# UperMachine.net
KiCad netlist of a schematic drawn in Altium Designer
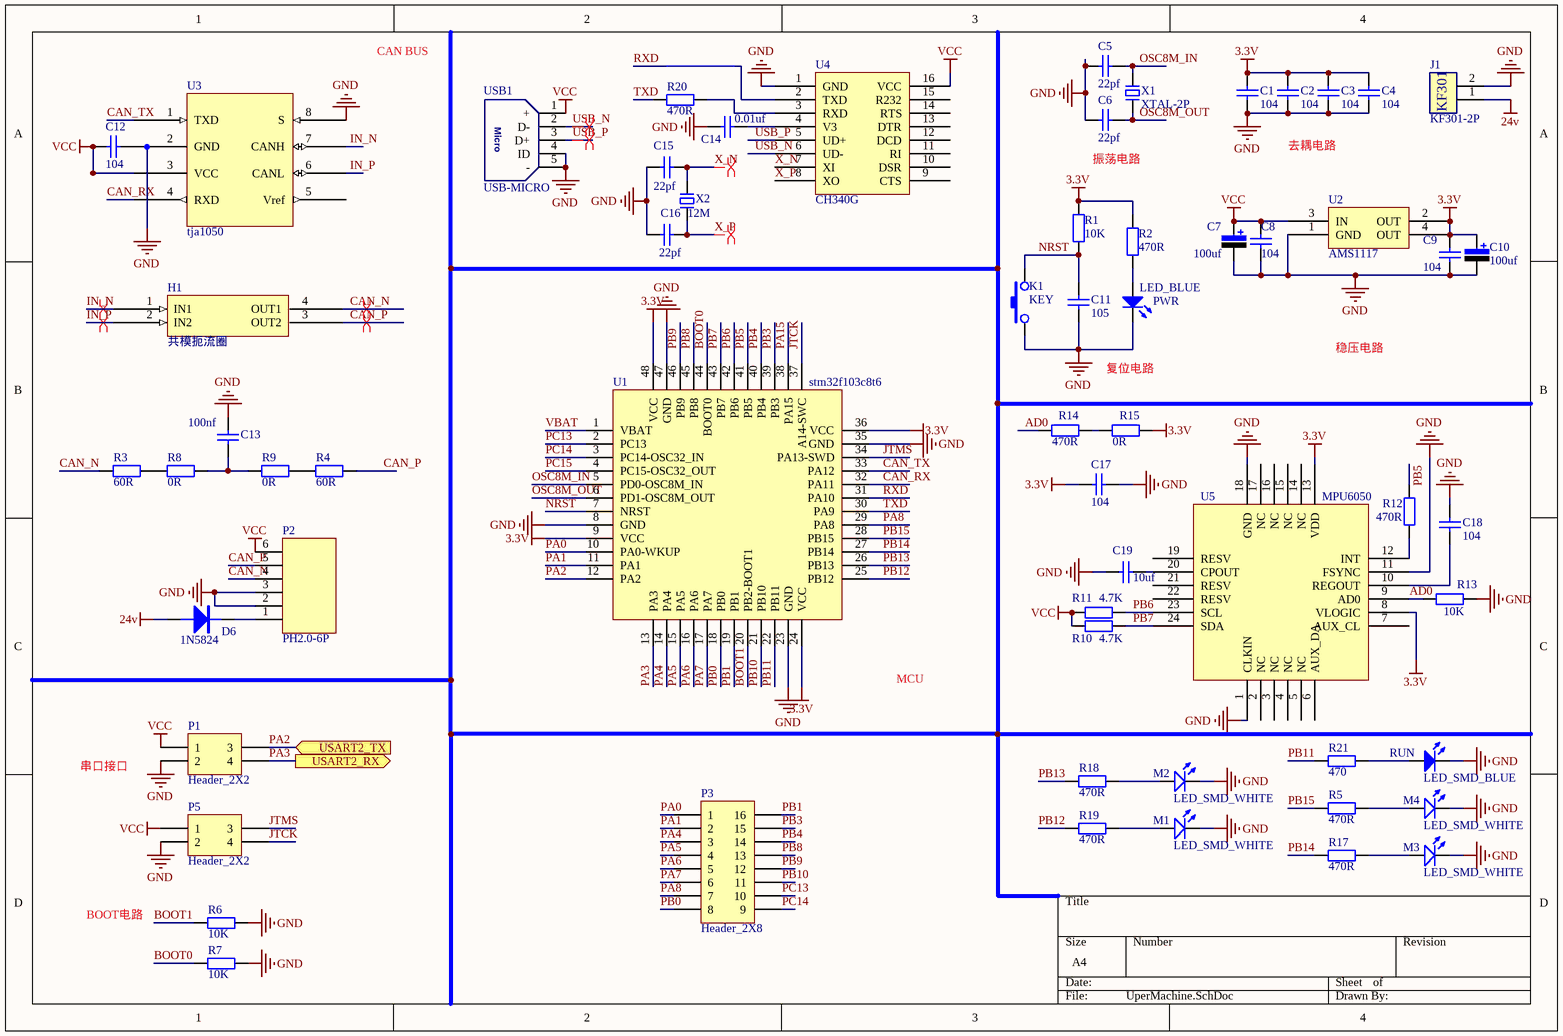
[diagram p0: UperMachine.SchDoc]

(export (version "E")
  (design (tool "Eeschema 10.0.6"))
  (components
    (comp (ref "C1") (value "104") (footprint "Cap-0603") (libsource (lib "最小系统元件库") (part "CAP")))
    (comp (ref "C2") (value "104") (footprint "Cap-0603") (libsource (lib "最小系统元件库") (part "CAP")))
    (comp (ref "C3") (value "104") (footprint "Cap-0603") (libsource (lib "最小系统元件库") (part "CAP")))
    (comp (ref "C4") (value "104") (footprint "Cap-0603") (libsource (lib "最小系统元件库") (part "CAP")))
    (comp (ref "C5") (value "22pf") (footprint "Cap-0603") (libsource (lib "最小系统元件库") (part "CAP")))
    (comp (ref "C6") (value "22pf") (footprint "Cap-0603") (libsource (lib "最小系统元件库") (part "CAP")))
    (comp (ref "C7") (value "100uf") (footprint "tan_cap_C") (libsource (lib "最小系统元件库") (part "tan_cap")))
    (comp (ref "C8") (value "104") (footprint "Cap-0603-M") (libsource (lib "最小系统元件库") (part "CAP")))
    (comp (ref "C9") (value "104") (footprint "Cap-0603-M") (libsource (lib "最小系统元件库") (part "CAP")))
    (comp (ref "C10") (value "100uf") (footprint "tan_cap_C") (libsource (lib "最小系统元件库") (part "tan_cap")))
    (comp (ref "C11") (value "105") (footprint "Cap-0603") (libsource (lib "最小系统元件库") (part "CAP")))
    (comp (ref "C12") (value "104") (footprint "Cap-0603") (libsource (lib "最小系统元件库") (part "CAP")))
    (comp (ref "C13") (value "100nf") (footprint "Cap-0603") (libsource (lib "最小系统元件库") (part "CAP")))
    (comp (ref "C14") (value "0.01uf") (footprint "Cap-0603") (libsource (lib "base") (part "Cap")))
    (comp (ref "C15") (value "22pf") (footprint "Cap-0603") (libsource (lib "最小系统元件库") (part "CAP")))
    (comp (ref "C16") (value "22pf") (footprint "Cap-0603") (libsource (lib "最小系统元件库") (part "CAP")))
    (comp (ref "C17") (value "104") (footprint "Cap-0603") (libsource (lib "最小系统元件库") (part "CAP")))
    (comp (ref "C18") (value "104") (footprint "Cap-0603") (libsource (lib "最小系统元件库") (part "CAP")))
    (comp (ref "C19") (value "10uf") (footprint "Cap-0603") (libsource (lib "最小系统元件库") (part "CAP")))
    (comp (ref "D6")
      (value "1N5824")
      (footprint "DO-214AC/SMA")
      (description "普通二极管")
      (libsource (lib "Miscellaneous Transistor") (part "DIODE"))
    )
    (comp (ref "H1") (value "共模扼流圈") (footprint "共模扼流圈") (libsource (lib "CAN步进控制板元件库") (part "共模扼流圈")))
    (comp (ref "J1")
      (value "KF301-2P")
      (footprint "KF301-5.0-2P")
      (libsource (lib "KF301") (part "KF301-2P"))
    )
    (comp (ref "K1")
      (value "KEY")
      (footprint "SW-SMD-2X4")
      (libsource (lib "Miscellaneous Switch") (part "KEY"))
    )
    (comp (ref "M1")
      (value "LED_SMD_WHITE")
      (footprint "LED_0603_W")
      (description "发光二极管")
      (libsource (lib "Miscellaneous Transistor") (part "LED_SMD_WHITE"))
    )
    (comp (ref "M2")
      (value "LED_SMD_WHITE")
      (footprint "LED_0603_W")
      (description "发光二极管")
      (libsource (lib "Miscellaneous Transistor") (part "LED_SMD_WHITE"))
    )
    (comp (ref "M3")
      (value "LED_SMD_WHITE")
      (footprint "LED_0603_W")
      (description "发光二极管")
      (libsource (lib "Miscellaneous Transistor") (part "LED_SMD_WHITE"))
    )
    (comp (ref "M4")
      (value "LED_SMD_WHITE")
      (footprint "LED_0603_W")
      (description "发光二极管")
      (libsource (lib "Miscellaneous Transistor") (part "LED_SMD_WHITE"))
    )
    (comp (ref "P1")
      (value "Header_2X2")
      (footprint "Header_SMD_2.54X2")
      (libsource (lib "Miscellaneous Header") (part "Header_2X2"))
    )
    (comp (ref "P2") (value "PH2.0-6P") (footprint "PH2.0S-6P") (libsource (lib "PH") (part "PH2.0-6P")))
    (comp (ref "P3")
      (value "Header_2X8")
      (footprint "Header_SMD_2.54X8")
      (libsource (lib "Miscellaneous Header") (part "Header_2X8"))
    )
    (comp (ref "P5")
      (value "Header_2X2")
      (footprint "Header_SMD_2.54X2")
      (libsource (lib "Miscellaneous Header") (part "Header_2X2"))
    )
    (comp (ref "PWR")
      (value "LED_BLUE")
      (footprint "LED_0603_B")
      (description "发光二极管")
      (libsource (lib "Miscellaneous Transistor") (part "LED_SMD_BLUE"))
    )
    (comp (ref "R1")
      (value "10K")
      (footprint "Res-0603")
      (description "贴片电阻")
      (libsource (lib "") (part "RES_2"))
    )
    (comp (ref "R2")
      (value "470R")
      (footprint "Res-0603")
      (description "贴片电阻")
      (libsource (lib "") (part "RES_2"))
    )
    (comp (ref "R3")
      (value "60R")
      (footprint "Res-0603")
      (description "贴片电阻")
      (libsource (lib "Miscellaneous Base") (part "RES"))
    )
    (comp (ref "R4")
      (value "60R")
      (footprint "Res-0603")
      (description "贴片电阻")
      (libsource (lib "Miscellaneous Base") (part "RES"))
    )
    (comp (ref "R5")
      (value "470R")
      (footprint "Res-0603")
      (description "贴片电阻")
      (libsource (lib "Miscellaneous Base") (part "RES"))
    )
    (comp (ref "R6")
      (value "10K")
      (footprint "Res-0603")
      (description "贴片电阻")
      (libsource (lib "Miscellaneous Base") (part "RES"))
    )
    (comp (ref "R7")
      (value "10K")
      (footprint "Res-0603")
      (description "贴片电阻")
      (libsource (lib "") (part "RES_1"))
    )
    (comp (ref "R8")
      (value "0R")
      (footprint "Res-0603")
      (description "贴片电阻")
      (libsource (lib "Miscellaneous Base") (part "RES"))
    )
    (comp (ref "R9")
      (value "0R")
      (footprint "Res-0603")
      (description "贴片电阻")
      (libsource (lib "Miscellaneous Base") (part "RES"))
    )
    (comp (ref "R10")
      (value "4.7K")
      (footprint "Res-0603")
      (description "贴片电阻")
      (libsource (lib "") (part "RES_1"))
    )
    (comp (ref "R11")
      (value "4.7K")
      (footprint "Res-0603")
      (description "贴片电阻")
      (libsource (lib "") (part "RES_1"))
    )
    (comp (ref "R12")
      (value "470R")
      (footprint "Res-0603")
      (description "贴片电阻")
      (libsource (lib "") (part "RES_2"))
    )
    (comp (ref "R13")
      (value "10K")
      (footprint "Res-0603")
      (description "贴片电阻")
      (libsource (lib "") (part "RES_1"))
    )
    (comp (ref "R14")
      (value "470R")
      (footprint "Res-0603")
      (description "贴片电阻")
      (libsource (lib "") (part "RES_1"))
    )
    (comp (ref "R15")
      (value "0R")
      (footprint "Res-0603")
      (description "贴片电阻")
      (libsource (lib "") (part "RES_1"))
    )
    (comp (ref "R17")
      (value "470R")
      (footprint "Res-0603")
      (description "贴片电阻")
      (libsource (lib "Miscellaneous Base") (part "RES"))
    )
    (comp (ref "R18")
      (value "470R")
      (footprint "Res-0603")
      (description "贴片电阻")
      (libsource (lib "Miscellaneous Base") (part "RES"))
    )
    (comp (ref "R19")
      (value "470R")
      (footprint "Res-0603")
      (description "贴片电阻")
      (libsource (lib "Miscellaneous Base") (part "RES"))
    )
    (comp (ref "R20")
      (value "470R")
      (footprint "Res-0603")
      (description "贴片电阻")
      (libsource (lib "Miscellaneous Base") (part "RES"))
    )
    (comp (ref "R21")
      (value "470")
      (footprint "Res-0603")
      (description "贴片电阻")
      (libsource (lib "Miscellaneous Base") (part "RES"))
    )
    (comp (ref "RUN")
      (value "LED_SMD_BLUE")
      (footprint "LED_0603_B")
      (description "发光二极管")
      (libsource (lib "") (part "LED_SMD_BLUE_1"))
    )
    (comp (ref "U1")
      (value "stm32f103c8t6")
      (footprint "stm32f103c8t6")
      (libsource (lib "最小系统元件库") (part "stm32f103c8t6"))
    )
    (comp (ref "U2") (value "AMS1117") (footprint "AMS1117") (libsource (lib "最小系统元件库") (part "AMS1117")))
    (comp (ref "U3") (value "tja1050") (footprint "tja1050") (libsource (lib "CAN步进控制板元件库") (part "tja1050")))
    (comp (ref "U4")
      (value "CH340G")
      (footprint "SOP127P590X265-16N")
      (libsource (lib "UperMachineLib") (part "CH340G"))
    )
    (comp (ref "U5")
      (value "MPU6050")
      (footprint "QFN50P400X400X95_HS-25N")
      (libsource (lib "UperMachineLib") (part "MPU6050"))
    )
    (comp (ref "USB1")
      (value "USB-MICRO")
      (footprint "USB-MICRO-SMD_C")
      (libsource (lib "Miscellaneous Socket") (part "USB-MICRO"))
    )
    (comp (ref "X1")
      (value "XTAL-2P")
      (footprint "OSC 5032-2P")
      (description "2脚无源脚晶振")
      (libsource (lib "Miscellaneous XTAL") (part "XTAL-2P"))
    )
    (comp (ref "X2")
      (value "12M")
      (footprint "OSC HC-49SMD")
      (description "2脚无源脚晶振")
      (libsource (lib "Miscellaneous XTAL") (part "XTAL-2P"))
    )
  )
  (nets
    (net (code "1") (name "/AD0") (class "Default")
      (node (ref "R13") (pin "2") (pinfunction "2_2") (pintype "passive"))
      (node (ref "R14") (pin "2") (pinfunction "2_2") (pintype "passive"))
      (node (ref "U5") (pin "9") (pinfunction "AD0_9") (pintype "passive"))
    )
    (net (code "2") (name "/BOOT0") (class "Default")
      (node (ref "R7") (pin "2") (pinfunction "2_2") (pintype "passive"))
      (node (ref "U1") (pin "44") (pinfunction "BOOT0_44") (pintype "passive"))
    )
    (net (code "3") (name "/BOOT1") (class "Default")
      (node (ref "R6") (pin "1") (pinfunction "1_1") (pintype "passive"))
      (node (ref "U1") (pin "20") (pinfunction "PB2-BOOT1_20") (pintype "passive"))
    )
    (net (code "4") (name "/CAN_N") (class "Default")
      (node (ref "H1") (pin "4") (pinfunction "OUT1_4") (pintype "passive"))
      (node (ref "P2") (pin "4") (pinfunction "4_4") (pintype "passive"))
      (node (ref "R3") (pin "1") (pinfunction "1_1") (pintype "passive"))
    )
    (net (code "5") (name "/CAN_P") (class "Default")
      (node (ref "H1") (pin "3") (pinfunction "OUT2_3") (pintype "passive"))
      (node (ref "P2") (pin "5") (pinfunction "5_5") (pintype "passive"))
      (node (ref "R4") (pin "2") (pinfunction "2_2") (pintype "passive"))
    )
    (net (code "6") (name "/CAN_RX") (class "Default")
      (node (ref "U1") (pin "32") (pinfunction "PA11_32") (pintype "passive"))
      (node (ref "U3") (pin "4") (pinfunction "RXD_4") (pintype "output"))
    )
    (net (code "7") (name "/CAN_TX") (class "Default")
      (node (ref "U1") (pin "33") (pinfunction "PA12_33") (pintype "passive"))
      (node (ref "U3") (pin "1") (pinfunction "TXD_1") (pintype "input"))
    )
    (net (code "8") (name "/IN_N") (class "Default")
      (node (ref "H1") (pin "1") (pinfunction "IN1_1") (pintype "input"))
      (node (ref "U3") (pin "7") (pinfunction "CANH_7") (pintype "bidirectional"))
    )
    (net (code "9") (name "/IN_P") (class "Default")
      (node (ref "H1") (pin "2") (pinfunction "IN2_2") (pintype "input"))
      (node (ref "U3") (pin "6") (pinfunction "CANL_6") (pintype "bidirectional"))
    )
    (net (code "10") (name "/JTCK") (class "Default")
      (node (ref "P5") (pin "4") (pinfunction "4_4") (pintype "passive"))
      (node (ref "U1") (pin "37") (pinfunction "A14-SWC_37") (pintype "passive"))
    )
    (net (code "11") (name "/JTMS") (class "Default")
      (node (ref "P5") (pin "3") (pinfunction "3_3") (pintype "passive"))
      (node (ref "U1") (pin "34") (pinfunction "PA13-SWD_34") (pintype "passive"))
    )
    (net (code "12") (name "/NRST") (class "Default")
      (node (ref "C11") (pin "2") (pinfunction "2_2") (pintype "passive"))
      (node (ref "K1") (pin "3") (pinfunction "3_3") (pintype "passive"))
      (node (ref "R1") (pin "2") (pinfunction "2_2") (pintype "passive"))
      (node (ref "U1") (pin "7") (pinfunction "NRST_7") (pintype "passive"))
    )
    (net (code "13") (name "/OSC8M_IN") (class "Default")
      (node (ref "C5") (pin "1") (pinfunction "1_1") (pintype "passive"))
      (node (ref "U1") (pin "5") (pinfunction "PD0-OSC8M_IN_5") (pintype "passive"))
      (node (ref "X1") (pin "2") (pinfunction "2_2") (pintype "passive"))
    )
    (net (code "14") (name "/OSC8M_OUT") (class "Default")
      (node (ref "C6") (pin "1") (pinfunction "1_1") (pintype "passive"))
      (node (ref "U1") (pin "6") (pinfunction "PD1-OSC8M_OUT_6") (pintype "passive"))
      (node (ref "X1") (pin "1") (pinfunction "1_1") (pintype "passive"))
    )
    (net (code "15") (name "/PA0") (class "Default")
      (node (ref "P3") (pin "1") (pinfunction "1_1") (pintype "power_in"))
      (node (ref "U1") (pin "10") (pinfunction "PA0-WKUP_10") (pintype "passive"))
    )
    (net (code "16") (name "/PA1") (class "Default")
      (node (ref "P3") (pin "2") (pinfunction "2_2") (pintype "power_in"))
      (node (ref "U1") (pin "11") (pinfunction "PA1_11") (pintype "passive"))
    )
    (net (code "17") (name "/PA2") (class "Default")
      (node (ref "P1") (pin "3") (pinfunction "3_3") (pintype "passive"))
      (node (ref "U1") (pin "12") (pinfunction "PA2_12") (pintype "passive"))
    )
    (net (code "18") (name "/PA3") (class "Default")
      (node (ref "P1") (pin "4") (pinfunction "4_4") (pintype "passive"))
      (node (ref "U1") (pin "13") (pinfunction "PA3_13") (pintype "passive"))
    )
    (net (code "19") (name "/PA4") (class "Default")
      (node (ref "P3") (pin "3") (pinfunction "3_3") (pintype "power_in"))
      (node (ref "U1") (pin "14") (pinfunction "PA4_14") (pintype "passive"))
    )
    (net (code "20") (name "/PA5") (class "Default")
      (node (ref "P3") (pin "4") (pinfunction "4_4") (pintype "power_in"))
      (node (ref "U1") (pin "15") (pinfunction "PA5_15") (pintype "passive"))
    )
    (net (code "21") (name "/PA6") (class "Default")
      (node (ref "P3") (pin "5") (pinfunction "5_5") (pintype "power_in"))
      (node (ref "U1") (pin "16") (pinfunction "PA6_16") (pintype "passive"))
    )
    (net (code "22") (name "/PA7") (class "Default")
      (node (ref "P3") (pin "6") (pinfunction "6_6") (pintype "power_in"))
      (node (ref "U1") (pin "17") (pinfunction "PA7_17") (pintype "passive"))
    )
    (net (code "23") (name "/PA8") (class "Default")
      (node (ref "P3") (pin "7") (pinfunction "7_7") (pintype "power_in"))
      (node (ref "U1") (pin "29") (pinfunction "PA8_29") (pintype "passive"))
    )
    (net (code "24") (name "/PA15") (class "Default")
      (node (ref "U1") (pin "38") (pinfunction "PA15_38") (pintype "passive"))
    )
    (net (code "25") (name "/PB0") (class "Default")
      (node (ref "P3") (pin "8") (pinfunction "8_8") (pintype "power_in"))
      (node (ref "U1") (pin "18") (pinfunction "PB0_18") (pintype "passive"))
    )
    (net (code "26") (name "/PB1") (class "Default")
      (node (ref "P3") (pin "16") (pinfunction "16_16") (pintype "power_in"))
      (node (ref "U1") (pin "19") (pinfunction "PB1_19") (pintype "passive"))
    )
    (net (code "27") (name "/PB3") (class "Default")
      (node (ref "P3") (pin "15") (pinfunction "15_15") (pintype "power_in"))
      (node (ref "U1") (pin "39") (pinfunction "PB3_39") (pintype "passive"))
    )
    (net (code "28") (name "/PB4") (class "Default")
      (node (ref "P3") (pin "14") (pinfunction "14_14") (pintype "power_in"))
      (node (ref "U1") (pin "40") (pinfunction "PB4_40") (pintype "passive"))
    )
    (net (code "29") (name "/PB5") (class "Default")
      (node (ref "R12") (pin "1") (pinfunction "1_1") (pintype "passive"))
      (node (ref "U1") (pin "41") (pinfunction "PB5_41") (pintype "passive"))
    )
    (net (code "30") (name "/PB6") (class "Default")
      (node (ref "R11") (pin "1") (pinfunction "1_1") (pintype "passive"))
      (node (ref "U1") (pin "42") (pinfunction "PB6_42") (pintype "passive"))
      (node (ref "U5") (pin "23") (pinfunction "SCL_23") (pintype "passive"))
    )
    (net (code "31") (name "/PB7") (class "Default")
      (node (ref "R10") (pin "1") (pinfunction "1_1") (pintype "passive"))
      (node (ref "U1") (pin "43") (pinfunction "PB7_43") (pintype "passive"))
      (node (ref "U5") (pin "24") (pinfunction "SDA_24") (pintype "passive"))
    )
    (net (code "32") (name "/PB8") (class "Default")
      (node (ref "P3") (pin "13") (pinfunction "13_13") (pintype "power_in"))
      (node (ref "U1") (pin "45") (pinfunction "PB8_45") (pintype "passive"))
    )
    (net (code "33") (name "/PB9") (class "Default")
      (node (ref "P3") (pin "12") (pinfunction "12_12") (pintype "power_in"))
      (node (ref "U1") (pin "46") (pinfunction "PB9_46") (pintype "passive"))
    )
    (net (code "34") (name "/PB10") (class "Default")
      (node (ref "P3") (pin "11") (pinfunction "11_11") (pintype "power_in"))
      (node (ref "U1") (pin "21") (pinfunction "PB10_21") (pintype "passive"))
    )
    (net (code "35") (name "/PB11") (class "Default")
      (node (ref "R21") (pin "1") (pinfunction "1_1") (pintype "passive"))
      (node (ref "U1") (pin "22") (pinfunction "PB11_22") (pintype "passive"))
    )
    (net (code "36") (name "/PB12") (class "Default")
      (node (ref "R19") (pin "1") (pinfunction "1_1") (pintype "passive"))
      (node (ref "U1") (pin "25") (pinfunction "PB12_25") (pintype "passive"))
    )
    (net (code "37") (name "/PB13") (class "Default")
      (node (ref "R18") (pin "1") (pinfunction "1_1") (pintype "passive"))
      (node (ref "U1") (pin "26") (pinfunction "PB13_26") (pintype "passive"))
    )
    (net (code "38") (name "/PB14") (class "Default")
      (node (ref "R17") (pin "1") (pinfunction "1_1") (pintype "passive"))
      (node (ref "U1") (pin "27") (pinfunction "PB14_27") (pintype "passive"))
    )
    (net (code "39") (name "/PB15") (class "Default")
      (node (ref "R5") (pin "1") (pinfunction "1_1") (pintype "passive"))
      (node (ref "U1") (pin "28") (pinfunction "PB15_28") (pintype "passive"))
    )
    (net (code "40") (name "/PC13") (class "Default")
      (node (ref "P3") (pin "10") (pinfunction "10_10") (pintype "power_in"))
      (node (ref "U1") (pin "2") (pinfunction "PC13_2") (pintype "passive"))
    )
    (net (code "41") (name "/PC14") (class "Default")
      (node (ref "P3") (pin "9") (pinfunction "9_9") (pintype "power_in"))
      (node (ref "U1") (pin "3") (pinfunction "PC14-OSC32_IN_3") (pintype "passive"))
    )
    (net (code "42") (name "/PC15") (class "Default")
      (node (ref "U1") (pin "4") (pinfunction "PC15-OSC32_OUT_4") (pintype "passive"))
    )
    (net (code "43") (name "/RXD") (class "Default")
      (node (ref "U1") (pin "31") (pinfunction "PA10_31") (pintype "passive"))
      (node (ref "U4") (pin "2") (pinfunction "TXD_2") (pintype "passive"))
    )
    (net (code "44") (name "/TXD") (class "Default")
      (node (ref "R20") (pin "1") (pinfunction "1_1") (pintype "passive"))
      (node (ref "U1") (pin "30") (pinfunction "PA9_30") (pintype "passive"))
    )
    (net (code "45") (name "/USB_N") (class "Default")
      (node (ref "U4") (pin "6") (pinfunction "UD-_6") (pintype "passive"))
      (node (ref "USB1") (pin "2") (pinfunction "D-_2") (pintype "passive"))
    )
    (net (code "46") (name "/USB_P") (class "Default")
      (node (ref "U4") (pin "5") (pinfunction "UD+_5") (pintype "passive"))
      (node (ref "USB1") (pin "3") (pinfunction "D+_3") (pintype "passive"))
    )
    (net (code "47") (name "/VBAT") (class "Default")
      (node (ref "U1") (pin "1") (pinfunction "VBAT_1") (pintype "passive"))
    )
    (net (code "48") (name "/X_N") (class "Default")
      (node (ref "C15") (pin "1") (pinfunction "1_1") (pintype "passive"))
      (node (ref "U4") (pin "7") (pinfunction "XI_7") (pintype "passive"))
      (node (ref "X2") (pin "1") (pinfunction "1_1") (pintype "passive"))
    )
    (net (code "49") (name "/X_P") (class "Default")
      (node (ref "C16") (pin "1") (pinfunction "1_1") (pintype "passive"))
      (node (ref "U4") (pin "8") (pinfunction "XO_8") (pintype "passive"))
      (node (ref "X2") (pin "2") (pinfunction "2_2") (pintype "passive"))
    )
    (net (code "50") (name "3.3V") (class "Default")
      (node (ref "C1") (pin "2") (pinfunction "2_2") (pintype "passive"))
      (node (ref "C10") (pin "1") (pinfunction "1_1") (pintype "passive"))
      (node (ref "C17") (pin "2") (pinfunction "2_2") (pintype "passive"))
      (node (ref "C2") (pin "2") (pinfunction "2_2") (pintype "passive"))
      (node (ref "C3") (pin "2") (pinfunction "2_2") (pintype "passive"))
      (node (ref "C4") (pin "2") (pinfunction "2_2") (pintype "passive"))
      (node (ref "C9") (pin "2") (pinfunction "2_2") (pintype "passive"))
      (node (ref "R1") (pin "1") (pinfunction "1_1") (pintype "passive"))
      (node (ref "R15") (pin "1") (pinfunction "1_1") (pintype "passive"))
      (node (ref "R2") (pin "1") (pinfunction "1_1") (pintype "passive"))
      (node (ref "U1") (pin "24") (pinfunction "VCC_24") (pintype "passive"))
      (node (ref "U1") (pin "36") (pinfunction "VCC_36") (pintype "passive"))
      (node (ref "U1") (pin "48") (pinfunction "VCC_48") (pintype "passive"))
      (node (ref "U1") (pin "9") (pinfunction "VCC_9") (pintype "passive"))
      (node (ref "U2") (pin "2") (pinfunction "OUT_2") (pintype "passive"))
      (node (ref "U2") (pin "4") (pinfunction "OUT_4") (pintype "passive"))
      (node (ref "U5") (pin "13") (pinfunction "VDD_13") (pintype "passive"))
      (node (ref "U5") (pin "8") (pinfunction "VLOGIC_8") (pintype "passive"))
    )
    (net (code "51") (name "24v") (class "Default")
      (node (ref "D6") (pin "A") (pinfunction "A_A") (pintype "passive"))
      (node (ref "J1") (pin "1") (pinfunction "1_1") (pintype "passive"))
    )
    (net (code "52") (name "GND") (class "Default")
      (node (ref "C1") (pin "1") (pinfunction "1_1") (pintype "passive"))
      (node (ref "C10") (pin "2") (pinfunction "2_2") (pintype "passive"))
      (node (ref "C11") (pin "1") (pinfunction "1_1") (pintype "passive"))
      (node (ref "C13") (pin "2") (pinfunction "2_2") (pintype "passive"))
      (node (ref "C14") (pin "1") (pinfunction "1_1") (pintype "passive"))
      (node (ref "C15") (pin "2") (pinfunction "2_2") (pintype "passive"))
      (node (ref "C16") (pin "2") (pinfunction "2_2") (pintype "passive"))
      (node (ref "C17") (pin "1") (pinfunction "1_1") (pintype "passive"))
      (node (ref "C18") (pin "1") (pinfunction "1_1") (pintype "passive"))
      (node (ref "C19") (pin "2") (pinfunction "2_2") (pintype "passive"))
      (node (ref "C2") (pin "1") (pinfunction "1_1") (pintype "passive"))
      (node (ref "C3") (pin "1") (pinfunction "1_1") (pintype "passive"))
      (node (ref "C4") (pin "1") (pinfunction "1_1") (pintype "passive"))
      (node (ref "C5") (pin "2") (pinfunction "2_2") (pintype "passive"))
      (node (ref "C6") (pin "2") (pinfunction "2_2") (pintype "passive"))
      (node (ref "C7") (pin "2") (pinfunction "2_2") (pintype "passive"))
      (node (ref "C8") (pin "1") (pinfunction "1_1") (pintype "passive"))
      (node (ref "C9") (pin "1") (pinfunction "1_1") (pintype "passive"))
      (node (ref "J1") (pin "2") (pinfunction "2_2") (pintype "passive"))
      (node (ref "K1") (pin "1") (pinfunction "1_1") (pintype "passive"))
      (node (ref "M1") (pin "2") (pinfunction "K_2") (pintype "passive"))
      (node (ref "M2") (pin "2") (pinfunction "K_2") (pintype "passive"))
      (node (ref "M3") (pin "2") (pinfunction "K_2") (pintype "passive"))
      (node (ref "M4") (pin "2") (pinfunction "K_2") (pintype "passive"))
      (node (ref "P1") (pin "2") (pinfunction "2_2") (pintype "passive"))
      (node (ref "P2") (pin "2") (pinfunction "2_2") (pintype "passive"))
      (node (ref "P2") (pin "3") (pinfunction "3_3") (pintype "passive"))
      (node (ref "P5") (pin "2") (pinfunction "2_2") (pintype "passive"))
      (node (ref "PWR") (pin "2") (pinfunction "K_2") (pintype "passive"))
      (node (ref "R13") (pin "1") (pinfunction "1_1") (pintype "passive"))
      (node (ref "R6") (pin "2") (pinfunction "2_2") (pintype "passive"))
      (node (ref "R7") (pin "1") (pinfunction "1_1") (pintype "passive"))
      (node (ref "RUN") (pin "2") (pinfunction "K_2") (pintype "passive"))
      (node (ref "U1") (pin "23") (pinfunction "GND_23") (pintype "passive"))
      (node (ref "U1") (pin "35") (pinfunction "GND_35") (pintype "passive"))
      (node (ref "U1") (pin "47") (pinfunction "GND_47") (pintype "passive"))
      (node (ref "U1") (pin "8") (pinfunction "GND_8") (pintype "passive"))
      (node (ref "U2") (pin "1") (pinfunction "GND_1") (pintype "passive"))
      (node (ref "U3") (pin "8") (pinfunction "S_8") (pintype "input"))
      (node (ref "U4") (pin "1") (pinfunction "GND_1") (pintype "passive"))
      (node (ref "U5") (pin "1") (pinfunction "CLKIN_1") (pintype "passive"))
      (node (ref "U5") (pin "11") (pinfunction "FSYNC_11") (pintype "passive"))
      (node (ref "U5") (pin "18") (pinfunction "GND_18") (pintype "passive"))
      (node (ref "USB1") (pin "4") (pinfunction "ID_4") (pintype "passive"))
      (node (ref "USB1") (pin "5") (pinfunction "-_5") (pintype "passive"))
    )
    (net (code "53") (name "Net-(C13-Pad1)") (class "Default")
      (node (ref "C13") (pin "1") (pinfunction "1_1") (pintype "passive"))
      (node (ref "R8") (pin "2") (pinfunction "2_2") (pintype "passive"))
      (node (ref "R9") (pin "1") (pinfunction "1_1") (pintype "passive"))
    )
    (net (code "54") (name "Net-(D6-PadK)") (class "Default")
      (node (ref "D6") (pin "K") (pinfunction "K_K") (pintype "passive"))
      (node (ref "P2") (pin "1") (pinfunction "1_1") (pintype "passive"))
    )
    (net (code "55") (name "Net-(M1-A)") (class "Default")
      (node (ref "M1") (pin "1") (pinfunction "A_1") (pintype "passive"))
      (node (ref "R19") (pin "2") (pinfunction "2_2") (pintype "passive"))
    )
    (net (code "56") (name "Net-(M2-A)") (class "Default")
      (node (ref "M2") (pin "1") (pinfunction "A_1") (pintype "passive"))
      (node (ref "R18") (pin "2") (pinfunction "2_2") (pintype "passive"))
    )
    (net (code "57") (name "Net-(M3-A)") (class "Default")
      (node (ref "M3") (pin "1") (pinfunction "A_1") (pintype "passive"))
      (node (ref "R17") (pin "2") (pinfunction "2_2") (pintype "passive"))
    )
    (net (code "58") (name "Net-(M4-A)") (class "Default")
      (node (ref "M4") (pin "1") (pinfunction "A_1") (pintype "passive"))
      (node (ref "R5") (pin "2") (pinfunction "2_2") (pintype "passive"))
    )
    (net (code "59") (name "Net-(PWR-A)") (class "Default")
      (node (ref "PWR") (pin "1") (pinfunction "A_1") (pintype "passive"))
      (node (ref "R2") (pin "2") (pinfunction "2_2") (pintype "passive"))
    )
    (net (code "60") (name "Net-(R3-Pad2)") (class "Default")
      (node (ref "R3") (pin "2") (pinfunction "2_2") (pintype "passive"))
      (node (ref "R8") (pin "1") (pinfunction "1_1") (pintype "passive"))
    )
    (net (code "61") (name "Net-(R4-Pad1)") (class "Default")
      (node (ref "R4") (pin "1") (pinfunction "1_1") (pintype "passive"))
      (node (ref "R9") (pin "2") (pinfunction "2_2") (pintype "passive"))
    )
    (net (code "62") (name "Net-(R14-Pad1)") (class "Default")
      (node (ref "R14") (pin "1") (pinfunction "1_1") (pintype "passive"))
      (node (ref "R15") (pin "2") (pinfunction "2_2") (pintype "passive"))
    )
    (net (code "63") (name "Net-(RUN-A)") (class "Default")
      (node (ref "R21") (pin "2") (pinfunction "2_2") (pintype "passive"))
      (node (ref "RUN") (pin "1") (pinfunction "A_1") (pintype "passive"))
    )
    (net (code "64") (name "Net-(U3-GND)") (class "Default")
      (node (ref "C12") (pin "2") (pinfunction "2_2") (pintype "passive"))
      (node (ref "U3") (pin "2") (pinfunction "GND_2") (pintype "power_in"))
    )
    (net (code "65") (name "Net-(U4-RXD)") (class "Default")
      (node (ref "R20") (pin "2") (pinfunction "2_2") (pintype "passive"))
      (node (ref "U4") (pin "3") (pinfunction "RXD_3") (pintype "passive"))
    )
    (net (code "66") (name "Net-(U4-V3)") (class "Default")
      (node (ref "C14") (pin "2") (pinfunction "2_2") (pintype "passive"))
      (node (ref "U4") (pin "4") (pinfunction "V3_4") (pintype "passive"))
    )
    (net (code "67") (name "Net-(U5-CPOUT)") (class "Default")
      (node (ref "C19") (pin "1") (pinfunction "1_1") (pintype "passive"))
      (node (ref "U5") (pin "20") (pinfunction "CPOUT_20") (pintype "passive"))
    )
    (net (code "68") (name "Net-(U5-INT)") (class "Default")
      (node (ref "R12") (pin "2") (pinfunction "2_2") (pintype "passive"))
      (node (ref "U5") (pin "12") (pinfunction "INT_12") (pintype "passive"))
    )
    (net (code "69") (name "Net-(U5-REGOUT)") (class "Default")
      (node (ref "C18") (pin "2") (pinfunction "2_2") (pintype "passive"))
      (node (ref "U5") (pin "10") (pinfunction "REGOUT_10") (pintype "passive"))
    )
    (net (code "70") (name "VCC") (class "Default")
      (node (ref "C12") (pin "1") (pinfunction "1_1") (pintype "passive"))
      (node (ref "C7") (pin "1") (pinfunction "1_1") (pintype "passive"))
      (node (ref "C8") (pin "2") (pinfunction "2_2") (pintype "passive"))
      (node (ref "P1") (pin "1") (pinfunction "1_1") (pintype "passive"))
      (node (ref "P2") (pin "6") (pinfunction "6_6") (pintype "passive"))
      (node (ref "P5") (pin "1") (pinfunction "1_1") (pintype "passive"))
      (node (ref "R10") (pin "2") (pinfunction "2_2") (pintype "passive"))
      (node (ref "R11") (pin "2") (pinfunction "2_2") (pintype "passive"))
      (node (ref "U2") (pin "3") (pinfunction "IN_3") (pintype "passive"))
      (node (ref "U3") (pin "3") (pinfunction "VCC_3") (pintype "power_in"))
      (node (ref "U4") (pin "16") (pinfunction "VCC_16") (pintype "passive"))
      (node (ref "USB1") (pin "1") (pinfunction "+_1") (pintype "passive"))
    )
    (net (code "71") (name "unconnected-(U3-Vref-Pad5)") (class "Default")
      (node (ref "U3") (pin "5") (pinfunction "Vref_5") (pintype "output"))
    )
    (net (code "72") (name "unconnected-(U4-CTS-Pad9)") (class "Default")
      (node (ref "U4") (pin "9") (pinfunction "CTS_9") (pintype "passive"))
    )
    (net (code "73") (name "unconnected-(U4-DCD-Pad12)") (class "Default")
      (node (ref "U4") (pin "12") (pinfunction "DCD_12") (pintype "passive"))
    )
    (net (code "74") (name "unconnected-(U4-DSR-Pad10)") (class "Default")
      (node (ref "U4") (pin "10") (pinfunction "DSR_10") (pintype "passive"))
    )
    (net (code "75") (name "unconnected-(U4-DTR-Pad13)") (class "Default")
      (node (ref "U4") (pin "13") (pinfunction "DTR_13") (pintype "passive"))
    )
    (net (code "76") (name "unconnected-(U4-R232-Pad15)") (class "Default")
      (node (ref "U4") (pin "15") (pinfunction "R232_15") (pintype "passive"))
    )
    (net (code "77") (name "unconnected-(U4-RI-Pad11)") (class "Default")
      (node (ref "U4") (pin "11") (pinfunction "RI_11") (pintype "passive"))
    )
    (net (code "78") (name "unconnected-(U4-RTS-Pad14)") (class "Default")
      (node (ref "U4") (pin "14") (pinfunction "RTS_14") (pintype "passive"))
    )
    (net (code "79") (name "unconnected-(U5-AUX_CL-Pad7)") (class "Default")
      (node (ref "U5") (pin "7") (pinfunction "AUX_CL_7") (pintype "passive"))
    )
    (net (code "80") (name "unconnected-(U5-AUX_DA-Pad6)") (class "Default")
      (node (ref "U5") (pin "6") (pinfunction "AUX_DA_6") (pintype "passive"))
    )
    (net (code "81") (name "unconnected-(U5-NC-Pad2)") (class "Default")
      (node (ref "U5") (pin "2") (pinfunction "NC_2") (pintype "passive"))
    )
    (net (code "82") (name "unconnected-(U5-NC-Pad3)") (class "Default")
      (node (ref "U5") (pin "3") (pinfunction "NC_3") (pintype "passive"))
    )
    (net (code "83") (name "unconnected-(U5-NC-Pad4)") (class "Default")
      (node (ref "U5") (pin "4") (pinfunction "NC_4") (pintype "passive"))
    )
    (net (code "84") (name "unconnected-(U5-NC-Pad5)") (class "Default")
      (node (ref "U5") (pin "5") (pinfunction "NC_5") (pintype "passive"))
    )
    (net (code "85") (name "unconnected-(U5-NC-Pad14)") (class "Default")
      (node (ref "U5") (pin "14") (pinfunction "NC_14") (pintype "passive"))
    )
    (net (code "86") (name "unconnected-(U5-NC-Pad15)") (class "Default")
      (node (ref "U5") (pin "15") (pinfunction "NC_15") (pintype "passive"))
    )
    (net (code "87") (name "unconnected-(U5-NC-Pad16)") (class "Default")
      (node (ref "U5") (pin "16") (pinfunction "NC_16") (pintype "passive"))
    )
    (net (code "88") (name "unconnected-(U5-NC-Pad17)") (class "Default")
      (node (ref "U5") (pin "17") (pinfunction "NC_17") (pintype "passive"))
    )
    (net (code "89") (name "unconnected-(U5-RESV-Pad19)") (class "Default")
      (node (ref "U5") (pin "19") (pinfunction "RESV_19") (pintype "passive"))
    )
    (net (code "90") (name "unconnected-(U5-RESV-Pad21)") (class "Default")
      (node (ref "U5") (pin "21") (pinfunction "RESV_21") (pintype "passive"))
    )
    (net (code "91") (name "unconnected-(U5-RESV-Pad22)") (class "Default")
      (node (ref "U5") (pin "22") (pinfunction "RESV_22") (pintype "passive"))
    )
  )
)
